# IO_board-ha-v1.net
KiCad netlist of a schematic drawn in EAGLE
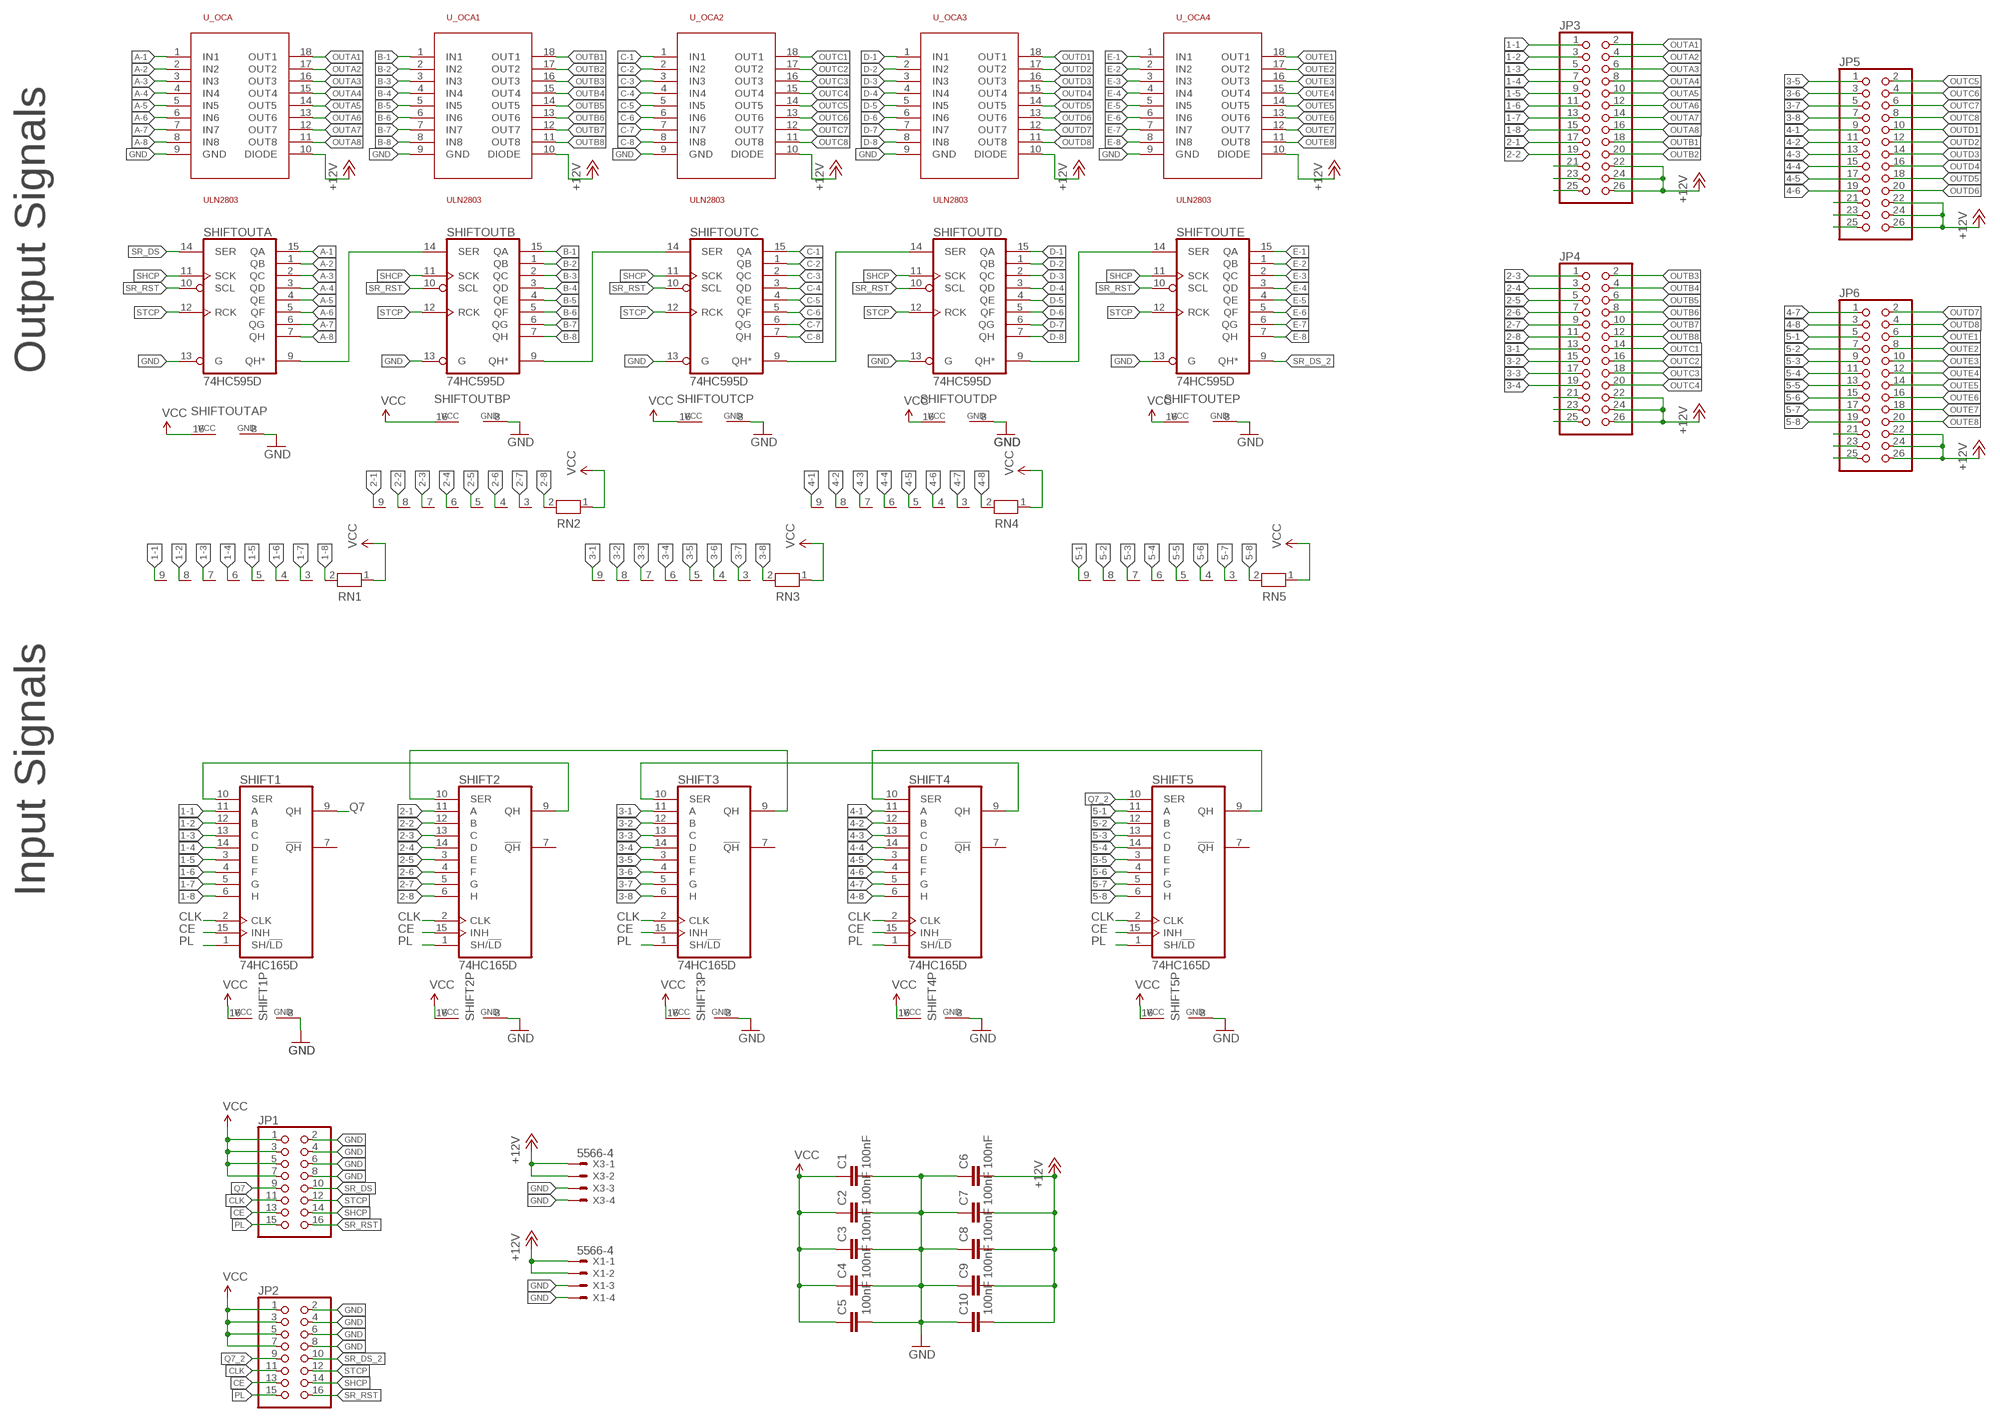
[diagram p0: schematic, sheet 1]

(export (version "E")
  (design (tool "Eeschema 10.0.6"))
  (components
    (comp (ref "C1")
      (value "100nF")
      (footprint "eagle-import:C0805")
      (libsource (lib "eagle-import") (part "C-EUC0805"))
    )
    (comp (ref "C2")
      (value "100nF")
      (footprint "eagle-import:C0805")
      (libsource (lib "eagle-import") (part "C-EUC0805"))
    )
    (comp (ref "C3")
      (value "100nF")
      (footprint "eagle-import:C0805")
      (libsource (lib "eagle-import") (part "C-EUC0805"))
    )
    (comp (ref "C4")
      (value "100nF")
      (footprint "eagle-import:C0805")
      (libsource (lib "eagle-import") (part "C-EUC0805"))
    )
    (comp (ref "C5")
      (value "100nF")
      (footprint "eagle-import:C0805")
      (libsource (lib "eagle-import") (part "C-EUC0805"))
    )
    (comp (ref "C6")
      (value "100nF")
      (footprint "eagle-import:C0805")
      (libsource (lib "eagle-import") (part "C-EUC0805"))
    )
    (comp (ref "C7")
      (value "100nF")
      (footprint "eagle-import:C0805")
      (libsource (lib "eagle-import") (part "C-EUC0805"))
    )
    (comp (ref "C8")
      (value "100nF")
      (footprint "eagle-import:C0805")
      (libsource (lib "eagle-import") (part "C-EUC0805"))
    )
    (comp (ref "C9")
      (value "100nF")
      (footprint "eagle-import:C0805")
      (libsource (lib "eagle-import") (part "C-EUC0805"))
    )
    (comp (ref "C10")
      (value "100nF")
      (footprint "eagle-import:C0805")
      (libsource (lib "eagle-import") (part "C-EUC0805"))
    )
    (comp (ref "JP1")
      (value "PINHD-2X8")
      (footprint "eagle-import:2X08")
      (libsource (lib "eagle-import") (part "PINHD-2X8"))
    )
    (comp (ref "JP2")
      (value "PINHD-2X8")
      (footprint "eagle-import:2X08")
      (libsource (lib "eagle-import") (part "PINHD-2X8"))
    )
    (comp (ref "JP3")
      (value "PINHD-2X13")
      (footprint "eagle-import:2X13")
      (libsource (lib "eagle-import") (part "PINHD-2X13"))
    )
    (comp (ref "JP4")
      (value "PINHD-2X13")
      (footprint "eagle-import:2X13")
      (libsource (lib "eagle-import") (part "PINHD-2X13"))
    )
    (comp (ref "JP5")
      (value "PINHD-2X13")
      (footprint "eagle-import:2X13")
      (libsource (lib "eagle-import") (part "PINHD-2X13"))
    )
    (comp (ref "JP6")
      (value "PINHD-2X13")
      (footprint "eagle-import:2X13")
      (libsource (lib "eagle-import") (part "PINHD-2X13"))
    )
    (comp (ref "RN1")
      (value "RN08")
      (footprint "eagle-import:RN-9")
      (libsource (lib "eagle-import") (part "RN08"))
    )
    (comp (ref "RN2")
      (value "RN08")
      (footprint "eagle-import:RN-9")
      (libsource (lib "eagle-import") (part "RN08"))
    )
    (comp (ref "RN3")
      (value "RN08")
      (footprint "eagle-import:RN-9")
      (libsource (lib "eagle-import") (part "RN08"))
    )
    (comp (ref "RN4")
      (value "RN08")
      (footprint "eagle-import:RN-9")
      (libsource (lib "eagle-import") (part "RN08"))
    )
    (comp (ref "RN5")
      (value "RN08")
      (footprint "eagle-import:RN-9")
      (libsource (lib "eagle-import") (part "RN08"))
    )
    (comp (ref "SHIFT1")
      (value "74HC165D")
      (footprint "eagle-import:SO16")
      (libsource (lib "eagle-import") (part "74165DHC"))
    )
    (comp (ref "SHIFT2")
      (value "74HC165D")
      (footprint "eagle-import:SO16")
      (libsource (lib "eagle-import") (part "74165DHC"))
    )
    (comp (ref "SHIFT3")
      (value "74HC165D")
      (footprint "eagle-import:SO16")
      (libsource (lib "eagle-import") (part "74165DHC"))
    )
    (comp (ref "SHIFT4")
      (value "74HC165D")
      (footprint "eagle-import:SO16")
      (libsource (lib "eagle-import") (part "74165DHC"))
    )
    (comp (ref "SHIFT5")
      (value "74HC165D")
      (footprint "eagle-import:SO16")
      (libsource (lib "eagle-import") (part "74165DHC"))
    )
    (comp (ref "SHIFTOUTA")
      (value "74HC595D")
      (footprint "eagle-import:SO16")
      (libsource (lib "eagle-import") (part "74595DHC"))
    )
    (comp (ref "SHIFTOUTB")
      (value "74HC595D")
      (footprint "eagle-import:SO16")
      (libsource (lib "eagle-import") (part "74595DHC"))
    )
    (comp (ref "SHIFTOUTC")
      (value "74HC595D")
      (footprint "eagle-import:SO16")
      (libsource (lib "eagle-import") (part "74595DHC"))
    )
    (comp (ref "SHIFTOUTD")
      (value "74HC595D")
      (footprint "eagle-import:SO16")
      (libsource (lib "eagle-import") (part "74595DHC"))
    )
    (comp (ref "SHIFTOUTE")
      (value "74HC595D")
      (footprint "eagle-import:SO16")
      (libsource (lib "eagle-import") (part "74595DHC"))
    )
    (comp (ref "U_OCA")
      (value "ULN2803")
      (footprint "eagle-import:SO18L")
      (libsource (lib "eagle-import") (part "ULN2803"))
    )
    (comp (ref "U_OCA1")
      (value "ULN2803")
      (footprint "eagle-import:SO18L")
      (libsource (lib "eagle-import") (part "ULN2803"))
    )
    (comp (ref "U_OCA2")
      (value "ULN2803")
      (footprint "eagle-import:SO18L")
      (libsource (lib "eagle-import") (part "ULN2803"))
    )
    (comp (ref "U_OCA3")
      (value "ULN2803")
      (footprint "eagle-import:SO18L")
      (libsource (lib "eagle-import") (part "ULN2803"))
    )
    (comp (ref "U_OCA4")
      (value "ULN2803")
      (footprint "eagle-import:SO18L")
      (libsource (lib "eagle-import") (part "ULN2803"))
    )
    (comp (ref "X1")
      (value "5566-4")
      (footprint "eagle-import:5566-4")
      (libsource (lib "eagle-import") (part "5566-4"))
    )
    (comp (ref "X3")
      (value "5566-4")
      (footprint "eagle-import:5566-4")
      (libsource (lib "eagle-import") (part "5566-4"))
    )
  )
  (nets
    (net (code "1") (name "+12V") (class "Default")
      (node (ref "C10") (pin "2") (pinfunction "2_2") (pintype "passive"))
      (node (ref "C6") (pin "2") (pinfunction "2_2") (pintype "passive"))
      (node (ref "C7") (pin "2") (pinfunction "2_2") (pintype "passive"))
      (node (ref "C8") (pin "2") (pinfunction "2_2") (pintype "passive"))
      (node (ref "C9") (pin "2") (pinfunction "2_2") (pintype "passive"))
      (node (ref "JP3") (pin "22") (pinfunction "22_22") (pintype "passive"))
      (node (ref "JP3") (pin "24") (pinfunction "24_24") (pintype "passive"))
      (node (ref "JP3") (pin "26") (pinfunction "26_26") (pintype "passive"))
      (node (ref "JP4") (pin "22") (pinfunction "22_22") (pintype "passive"))
      (node (ref "JP4") (pin "24") (pinfunction "24_24") (pintype "passive"))
      (node (ref "JP4") (pin "26") (pinfunction "26_26") (pintype "passive"))
      (node (ref "JP5") (pin "22") (pinfunction "22_22") (pintype "passive"))
      (node (ref "JP5") (pin "24") (pinfunction "24_24") (pintype "passive"))
      (node (ref "JP5") (pin "26") (pinfunction "26_26") (pintype "passive"))
      (node (ref "JP6") (pin "22") (pinfunction "22_22") (pintype "passive"))
      (node (ref "JP6") (pin "24") (pinfunction "24_24") (pintype "passive"))
      (node (ref "JP6") (pin "26") (pinfunction "26_26") (pintype "passive"))
      (node (ref "U_OCA") (pin "10") (pinfunction "DIODE_10") (pintype "power_in"))
      (node (ref "U_OCA1") (pin "10") (pinfunction "DIODE_10") (pintype "power_in"))
      (node (ref "U_OCA2") (pin "10") (pinfunction "DIODE_10") (pintype "power_in"))
      (node (ref "U_OCA3") (pin "10") (pinfunction "DIODE_10") (pintype "power_in"))
      (node (ref "U_OCA4") (pin "10") (pinfunction "DIODE_10") (pintype "power_in"))
      (node (ref "X1") (pin "1") (pinfunction "S_1") (pintype "passive"))
      (node (ref "X1") (pin "2") (pinfunction "S_2") (pintype "passive"))
      (node (ref "X3") (pin "1") (pinfunction "S_1") (pintype "passive"))
      (node (ref "X3") (pin "2") (pinfunction "S_2") (pintype "passive"))
    )
    (net (code "2") (name "1-1") (class "Default")
      (node (ref "JP3") (pin "1") (pinfunction "1_1") (pintype "passive"))
      (node (ref "RN1") (pin "9") (pinfunction "9_9") (pintype "passive"))
      (node (ref "SHIFT1") (pin "11") (pinfunction "A_11") (pintype "input"))
    )
    (net (code "3") (name "1-2") (class "Default")
      (node (ref "JP3") (pin "3") (pinfunction "3_3") (pintype "passive"))
      (node (ref "RN1") (pin "8") (pinfunction "8_8") (pintype "passive"))
      (node (ref "SHIFT1") (pin "12") (pinfunction "B_12") (pintype "input"))
    )
    (net (code "4") (name "1-3") (class "Default")
      (node (ref "JP3") (pin "5") (pinfunction "5_5") (pintype "passive"))
      (node (ref "RN1") (pin "7") (pinfunction "7_7") (pintype "passive"))
      (node (ref "SHIFT1") (pin "13") (pinfunction "C_13") (pintype "input"))
    )
    (net (code "5") (name "1-4") (class "Default")
      (node (ref "JP3") (pin "7") (pinfunction "7_7") (pintype "passive"))
      (node (ref "RN1") (pin "6") (pinfunction "6_6") (pintype "passive"))
      (node (ref "SHIFT1") (pin "14") (pinfunction "D_14") (pintype "input"))
    )
    (net (code "6") (name "1-5") (class "Default")
      (node (ref "JP3") (pin "9") (pinfunction "9_9") (pintype "passive"))
      (node (ref "RN1") (pin "5") (pinfunction "5_5") (pintype "passive"))
      (node (ref "SHIFT1") (pin "3") (pinfunction "E_3") (pintype "input"))
    )
    (net (code "7") (name "1-6") (class "Default")
      (node (ref "JP3") (pin "11") (pinfunction "11_11") (pintype "passive"))
      (node (ref "RN1") (pin "4") (pinfunction "4_4") (pintype "passive"))
      (node (ref "SHIFT1") (pin "4") (pinfunction "F_4") (pintype "input"))
    )
    (net (code "8") (name "1-7") (class "Default")
      (node (ref "JP3") (pin "13") (pinfunction "13_13") (pintype "passive"))
      (node (ref "RN1") (pin "3") (pinfunction "3_3") (pintype "passive"))
      (node (ref "SHIFT1") (pin "5") (pinfunction "G_5") (pintype "input"))
    )
    (net (code "9") (name "1-8") (class "Default")
      (node (ref "JP3") (pin "15") (pinfunction "15_15") (pintype "passive"))
      (node (ref "RN1") (pin "2") (pinfunction "2_2") (pintype "passive"))
      (node (ref "SHIFT1") (pin "6") (pinfunction "H_6") (pintype "input"))
    )
    (net (code "10") (name "2-1") (class "Default")
      (node (ref "JP3") (pin "17") (pinfunction "17_17") (pintype "passive"))
      (node (ref "RN2") (pin "9") (pinfunction "9_9") (pintype "passive"))
      (node (ref "SHIFT2") (pin "11") (pinfunction "A_11") (pintype "input"))
    )
    (net (code "11") (name "2-2") (class "Default")
      (node (ref "JP3") (pin "19") (pinfunction "19_19") (pintype "passive"))
      (node (ref "RN2") (pin "8") (pinfunction "8_8") (pintype "passive"))
      (node (ref "SHIFT2") (pin "12") (pinfunction "B_12") (pintype "input"))
    )
    (net (code "12") (name "2-3") (class "Default")
      (node (ref "JP4") (pin "1") (pinfunction "1_1") (pintype "passive"))
      (node (ref "RN2") (pin "7") (pinfunction "7_7") (pintype "passive"))
      (node (ref "SHIFT2") (pin "13") (pinfunction "C_13") (pintype "input"))
    )
    (net (code "13") (name "2-4") (class "Default")
      (node (ref "JP4") (pin "3") (pinfunction "3_3") (pintype "passive"))
      (node (ref "RN2") (pin "6") (pinfunction "6_6") (pintype "passive"))
      (node (ref "SHIFT2") (pin "14") (pinfunction "D_14") (pintype "input"))
    )
    (net (code "14") (name "2-5") (class "Default")
      (node (ref "JP4") (pin "5") (pinfunction "5_5") (pintype "passive"))
      (node (ref "RN2") (pin "5") (pinfunction "5_5") (pintype "passive"))
      (node (ref "SHIFT2") (pin "3") (pinfunction "E_3") (pintype "input"))
    )
    (net (code "15") (name "2-6") (class "Default")
      (node (ref "JP4") (pin "7") (pinfunction "7_7") (pintype "passive"))
      (node (ref "RN2") (pin "4") (pinfunction "4_4") (pintype "passive"))
      (node (ref "SHIFT2") (pin "4") (pinfunction "F_4") (pintype "input"))
    )
    (net (code "16") (name "2-7") (class "Default")
      (node (ref "JP4") (pin "9") (pinfunction "9_9") (pintype "passive"))
      (node (ref "RN2") (pin "3") (pinfunction "3_3") (pintype "passive"))
      (node (ref "SHIFT2") (pin "5") (pinfunction "G_5") (pintype "input"))
    )
    (net (code "17") (name "2-8") (class "Default")
      (node (ref "JP4") (pin "11") (pinfunction "11_11") (pintype "passive"))
      (node (ref "RN2") (pin "2") (pinfunction "2_2") (pintype "passive"))
      (node (ref "SHIFT2") (pin "6") (pinfunction "H_6") (pintype "input"))
    )
    (net (code "18") (name "3-1") (class "Default")
      (node (ref "JP4") (pin "13") (pinfunction "13_13") (pintype "passive"))
      (node (ref "RN3") (pin "9") (pinfunction "9_9") (pintype "passive"))
      (node (ref "SHIFT3") (pin "11") (pinfunction "A_11") (pintype "input"))
    )
    (net (code "19") (name "3-2") (class "Default")
      (node (ref "JP4") (pin "15") (pinfunction "15_15") (pintype "passive"))
      (node (ref "RN3") (pin "8") (pinfunction "8_8") (pintype "passive"))
      (node (ref "SHIFT3") (pin "12") (pinfunction "B_12") (pintype "input"))
    )
    (net (code "20") (name "3-3") (class "Default")
      (node (ref "JP4") (pin "17") (pinfunction "17_17") (pintype "passive"))
      (node (ref "RN3") (pin "7") (pinfunction "7_7") (pintype "passive"))
      (node (ref "SHIFT3") (pin "13") (pinfunction "C_13") (pintype "input"))
    )
    (net (code "21") (name "3-4") (class "Default")
      (node (ref "JP4") (pin "19") (pinfunction "19_19") (pintype "passive"))
      (node (ref "RN3") (pin "6") (pinfunction "6_6") (pintype "passive"))
      (node (ref "SHIFT3") (pin "14") (pinfunction "D_14") (pintype "input"))
    )
    (net (code "22") (name "3-5") (class "Default")
      (node (ref "JP5") (pin "1") (pinfunction "1_1") (pintype "passive"))
      (node (ref "RN3") (pin "5") (pinfunction "5_5") (pintype "passive"))
      (node (ref "SHIFT3") (pin "3") (pinfunction "E_3") (pintype "input"))
    )
    (net (code "23") (name "3-6") (class "Default")
      (node (ref "JP5") (pin "3") (pinfunction "3_3") (pintype "passive"))
      (node (ref "RN3") (pin "4") (pinfunction "4_4") (pintype "passive"))
      (node (ref "SHIFT3") (pin "4") (pinfunction "F_4") (pintype "input"))
    )
    (net (code "24") (name "3-7") (class "Default")
      (node (ref "JP5") (pin "5") (pinfunction "5_5") (pintype "passive"))
      (node (ref "RN3") (pin "3") (pinfunction "3_3") (pintype "passive"))
      (node (ref "SHIFT3") (pin "5") (pinfunction "G_5") (pintype "input"))
    )
    (net (code "25") (name "3-8") (class "Default")
      (node (ref "JP5") (pin "7") (pinfunction "7_7") (pintype "passive"))
      (node (ref "RN3") (pin "2") (pinfunction "2_2") (pintype "passive"))
      (node (ref "SHIFT3") (pin "6") (pinfunction "H_6") (pintype "input"))
    )
    (net (code "26") (name "4-1") (class "Default")
      (node (ref "JP5") (pin "9") (pinfunction "9_9") (pintype "passive"))
      (node (ref "RN4") (pin "9") (pinfunction "9_9") (pintype "passive"))
      (node (ref "SHIFT4") (pin "11") (pinfunction "A_11") (pintype "input"))
    )
    (net (code "27") (name "4-2") (class "Default")
      (node (ref "JP5") (pin "11") (pinfunction "11_11") (pintype "passive"))
      (node (ref "RN4") (pin "8") (pinfunction "8_8") (pintype "passive"))
      (node (ref "SHIFT4") (pin "12") (pinfunction "B_12") (pintype "input"))
    )
    (net (code "28") (name "4-3") (class "Default")
      (node (ref "JP5") (pin "13") (pinfunction "13_13") (pintype "passive"))
      (node (ref "RN4") (pin "7") (pinfunction "7_7") (pintype "passive"))
      (node (ref "SHIFT4") (pin "13") (pinfunction "C_13") (pintype "input"))
    )
    (net (code "29") (name "4-4") (class "Default")
      (node (ref "JP5") (pin "15") (pinfunction "15_15") (pintype "passive"))
      (node (ref "RN4") (pin "6") (pinfunction "6_6") (pintype "passive"))
      (node (ref "SHIFT4") (pin "14") (pinfunction "D_14") (pintype "input"))
    )
    (net (code "30") (name "4-5") (class "Default")
      (node (ref "JP5") (pin "17") (pinfunction "17_17") (pintype "passive"))
      (node (ref "RN4") (pin "5") (pinfunction "5_5") (pintype "passive"))
      (node (ref "SHIFT4") (pin "3") (pinfunction "E_3") (pintype "input"))
    )
    (net (code "31") (name "4-6") (class "Default")
      (node (ref "JP5") (pin "19") (pinfunction "19_19") (pintype "passive"))
      (node (ref "RN4") (pin "4") (pinfunction "4_4") (pintype "passive"))
      (node (ref "SHIFT4") (pin "4") (pinfunction "F_4") (pintype "input"))
    )
    (net (code "32") (name "4-7") (class "Default")
      (node (ref "JP6") (pin "1") (pinfunction "1_1") (pintype "passive"))
      (node (ref "RN4") (pin "3") (pinfunction "3_3") (pintype "passive"))
      (node (ref "SHIFT4") (pin "5") (pinfunction "G_5") (pintype "input"))
    )
    (net (code "33") (name "4-8") (class "Default")
      (node (ref "JP6") (pin "3") (pinfunction "3_3") (pintype "passive"))
      (node (ref "RN4") (pin "2") (pinfunction "2_2") (pintype "passive"))
      (node (ref "SHIFT4") (pin "6") (pinfunction "H_6") (pintype "input"))
    )
    (net (code "34") (name "5-1") (class "Default")
      (node (ref "JP6") (pin "5") (pinfunction "5_5") (pintype "passive"))
      (node (ref "RN5") (pin "9") (pinfunction "9_9") (pintype "passive"))
      (node (ref "SHIFT5") (pin "11") (pinfunction "A_11") (pintype "input"))
    )
    (net (code "35") (name "5-2") (class "Default")
      (node (ref "JP6") (pin "7") (pinfunction "7_7") (pintype "passive"))
      (node (ref "RN5") (pin "8") (pinfunction "8_8") (pintype "passive"))
      (node (ref "SHIFT5") (pin "12") (pinfunction "B_12") (pintype "input"))
    )
    (net (code "36") (name "5-3") (class "Default")
      (node (ref "JP6") (pin "9") (pinfunction "9_9") (pintype "passive"))
      (node (ref "RN5") (pin "7") (pinfunction "7_7") (pintype "passive"))
      (node (ref "SHIFT5") (pin "13") (pinfunction "C_13") (pintype "input"))
    )
    (net (code "37") (name "5-4") (class "Default")
      (node (ref "JP6") (pin "11") (pinfunction "11_11") (pintype "passive"))
      (node (ref "RN5") (pin "6") (pinfunction "6_6") (pintype "passive"))
      (node (ref "SHIFT5") (pin "14") (pinfunction "D_14") (pintype "input"))
    )
    (net (code "38") (name "5-5") (class "Default")
      (node (ref "JP6") (pin "13") (pinfunction "13_13") (pintype "passive"))
      (node (ref "RN5") (pin "5") (pinfunction "5_5") (pintype "passive"))
      (node (ref "SHIFT5") (pin "3") (pinfunction "E_3") (pintype "input"))
    )
    (net (code "39") (name "5-6") (class "Default")
      (node (ref "JP6") (pin "15") (pinfunction "15_15") (pintype "passive"))
      (node (ref "RN5") (pin "4") (pinfunction "4_4") (pintype "passive"))
      (node (ref "SHIFT5") (pin "4") (pinfunction "F_4") (pintype "input"))
    )
    (net (code "40") (name "5-7") (class "Default")
      (node (ref "JP6") (pin "17") (pinfunction "17_17") (pintype "passive"))
      (node (ref "RN5") (pin "3") (pinfunction "3_3") (pintype "passive"))
      (node (ref "SHIFT5") (pin "5") (pinfunction "G_5") (pintype "input"))
    )
    (net (code "41") (name "5-8") (class "Default")
      (node (ref "JP6") (pin "19") (pinfunction "19_19") (pintype "passive"))
      (node (ref "RN5") (pin "2") (pinfunction "2_2") (pintype "passive"))
      (node (ref "SHIFT5") (pin "6") (pinfunction "H_6") (pintype "input"))
    )
    (net (code "42") (name "A-1") (class "Default")
      (node (ref "SHIFTOUTA") (pin "15") (pinfunction "QA_15") (pintype "tri_state"))
      (node (ref "U_OCA") (pin "1") (pinfunction "IN1_1") (pintype "input"))
    )
    (net (code "43") (name "A-2") (class "Default")
      (node (ref "SHIFTOUTA") (pin "1") (pinfunction "QB_1") (pintype "tri_state"))
      (node (ref "U_OCA") (pin "2") (pinfunction "IN2_2") (pintype "input"))
    )
    (net (code "44") (name "A-3") (class "Default")
      (node (ref "SHIFTOUTA") (pin "2") (pinfunction "QC_2") (pintype "tri_state"))
      (node (ref "U_OCA") (pin "3") (pinfunction "IN3_3") (pintype "input"))
    )
    (net (code "45") (name "A-4") (class "Default")
      (node (ref "SHIFTOUTA") (pin "3") (pinfunction "QD_3") (pintype "tri_state"))
      (node (ref "U_OCA") (pin "4") (pinfunction "IN4_4") (pintype "input"))
    )
    (net (code "46") (name "A-5") (class "Default")
      (node (ref "SHIFTOUTA") (pin "4") (pinfunction "QE_4") (pintype "tri_state"))
      (node (ref "U_OCA") (pin "5") (pinfunction "IN5_5") (pintype "input"))
    )
    (net (code "47") (name "A-6") (class "Default")
      (node (ref "SHIFTOUTA") (pin "5") (pinfunction "QF_5") (pintype "tri_state"))
      (node (ref "U_OCA") (pin "6") (pinfunction "IN6_6") (pintype "input"))
    )
    (net (code "48") (name "A-7") (class "Default")
      (node (ref "SHIFTOUTA") (pin "6") (pinfunction "QG_6") (pintype "tri_state"))
      (node (ref "U_OCA") (pin "7") (pinfunction "IN7_7") (pintype "input"))
    )
    (net (code "49") (name "A-8") (class "Default")
      (node (ref "SHIFTOUTA") (pin "7") (pinfunction "QH_7") (pintype "tri_state"))
      (node (ref "U_OCA") (pin "8") (pinfunction "IN8_8") (pintype "input"))
    )
    (net (code "50") (name "B-1") (class "Default")
      (node (ref "SHIFTOUTB") (pin "15") (pinfunction "QA_15") (pintype "tri_state"))
      (node (ref "U_OCA1") (pin "1") (pinfunction "IN1_1") (pintype "input"))
    )
    (net (code "51") (name "B-2") (class "Default")
      (node (ref "SHIFTOUTB") (pin "1") (pinfunction "QB_1") (pintype "tri_state"))
      (node (ref "U_OCA1") (pin "2") (pinfunction "IN2_2") (pintype "input"))
    )
    (net (code "52") (name "B-3") (class "Default")
      (node (ref "SHIFTOUTB") (pin "2") (pinfunction "QC_2") (pintype "tri_state"))
      (node (ref "U_OCA1") (pin "3") (pinfunction "IN3_3") (pintype "input"))
    )
    (net (code "53") (name "B-4") (class "Default")
      (node (ref "SHIFTOUTB") (pin "3") (pinfunction "QD_3") (pintype "tri_state"))
      (node (ref "U_OCA1") (pin "4") (pinfunction "IN4_4") (pintype "input"))
    )
    (net (code "54") (name "B-5") (class "Default")
      (node (ref "SHIFTOUTB") (pin "4") (pinfunction "QE_4") (pintype "tri_state"))
      (node (ref "U_OCA1") (pin "5") (pinfunction "IN5_5") (pintype "input"))
    )
    (net (code "55") (name "B-6") (class "Default")
      (node (ref "SHIFTOUTB") (pin "5") (pinfunction "QF_5") (pintype "tri_state"))
      (node (ref "U_OCA1") (pin "6") (pinfunction "IN6_6") (pintype "input"))
    )
    (net (code "56") (name "B-7") (class "Default")
      (node (ref "SHIFTOUTB") (pin "6") (pinfunction "QG_6") (pintype "tri_state"))
      (node (ref "U_OCA1") (pin "7") (pinfunction "IN7_7") (pintype "input"))
    )
    (net (code "57") (name "B-8") (class "Default")
      (node (ref "SHIFTOUTB") (pin "7") (pinfunction "QH_7") (pintype "tri_state"))
      (node (ref "U_OCA1") (pin "8") (pinfunction "IN8_8") (pintype "input"))
    )
    (net (code "58") (name "C-1") (class "Default")
      (node (ref "SHIFTOUTC") (pin "15") (pinfunction "QA_15") (pintype "tri_state"))
      (node (ref "U_OCA2") (pin "1") (pinfunction "IN1_1") (pintype "input"))
    )
    (net (code "59") (name "C-2") (class "Default")
      (node (ref "SHIFTOUTC") (pin "1") (pinfunction "QB_1") (pintype "tri_state"))
      (node (ref "U_OCA2") (pin "2") (pinfunction "IN2_2") (pintype "input"))
    )
    (net (code "60") (name "C-3") (class "Default")
      (node (ref "SHIFTOUTC") (pin "2") (pinfunction "QC_2") (pintype "tri_state"))
      (node (ref "U_OCA2") (pin "3") (pinfunction "IN3_3") (pintype "input"))
    )
    (net (code "61") (name "C-4") (class "Default")
      (node (ref "SHIFTOUTC") (pin "3") (pinfunction "QD_3") (pintype "tri_state"))
      (node (ref "U_OCA2") (pin "4") (pinfunction "IN4_4") (pintype "input"))
    )
    (net (code "62") (name "C-5") (class "Default")
      (node (ref "SHIFTOUTC") (pin "4") (pinfunction "QE_4") (pintype "tri_state"))
      (node (ref "U_OCA2") (pin "5") (pinfunction "IN5_5") (pintype "input"))
    )
    (net (code "63") (name "C-6") (class "Default")
      (node (ref "SHIFTOUTC") (pin "5") (pinfunction "QF_5") (pintype "tri_state"))
      (node (ref "U_OCA2") (pin "6") (pinfunction "IN6_6") (pintype "input"))
    )
    (net (code "64") (name "C-7") (class "Default")
      (node (ref "SHIFTOUTC") (pin "6") (pinfunction "QG_6") (pintype "tri_state"))
      (node (ref "U_OCA2") (pin "7") (pinfunction "IN7_7") (pintype "input"))
    )
    (net (code "65") (name "C-8") (class "Default")
      (node (ref "SHIFTOUTC") (pin "7") (pinfunction "QH_7") (pintype "tri_state"))
      (node (ref "U_OCA2") (pin "8") (pinfunction "IN8_8") (pintype "input"))
    )
    (net (code "66") (name "CE") (class "Default")
      (node (ref "JP1") (pin "13") (pinfunction "13_13") (pintype "passive"))
      (node (ref "JP2") (pin "13") (pinfunction "13_13") (pintype "passive"))
      (node (ref "SHIFT1") (pin "15") (pinfunction "INH_15") (pintype "input"))
      (node (ref "SHIFT2") (pin "15") (pinfunction "INH_15") (pintype "input"))
      (node (ref "SHIFT3") (pin "15") (pinfunction "INH_15") (pintype "input"))
      (node (ref "SHIFT4") (pin "15") (pinfunction "INH_15") (pintype "input"))
      (node (ref "SHIFT5") (pin "15") (pinfunction "INH_15") (pintype "input"))
    )
    (net (code "67") (name "CLK") (class "Default")
      (node (ref "JP1") (pin "11") (pinfunction "11_11") (pintype "passive"))
      (node (ref "JP2") (pin "11") (pinfunction "11_11") (pintype "passive"))
      (node (ref "SHIFT1") (pin "2") (pinfunction "CLK_2") (pintype "input"))
      (node (ref "SHIFT2") (pin "2") (pinfunction "CLK_2") (pintype "input"))
      (node (ref "SHIFT3") (pin "2") (pinfunction "CLK_2") (pintype "input"))
      (node (ref "SHIFT4") (pin "2") (pinfunction "CLK_2") (pintype "input"))
      (node (ref "SHIFT5") (pin "2") (pinfunction "CLK_2") (pintype "input"))
    )
    (net (code "68") (name "D-1") (class "Default")
      (node (ref "SHIFTOUTD") (pin "15") (pinfunction "QA_15") (pintype "tri_state"))
      (node (ref "U_OCA3") (pin "1") (pinfunction "IN1_1") (pintype "input"))
    )
    (net (code "69") (name "D-2") (class "Default")
      (node (ref "SHIFTOUTD") (pin "1") (pinfunction "QB_1") (pintype "tri_state"))
      (node (ref "U_OCA3") (pin "2") (pinfunction "IN2_2") (pintype "input"))
    )
    (net (code "70") (name "D-3") (class "Default")
      (node (ref "SHIFTOUTD") (pin "2") (pinfunction "QC_2") (pintype "tri_state"))
      (node (ref "U_OCA3") (pin "3") (pinfunction "IN3_3") (pintype "input"))
    )
    (net (code "71") (name "D-4") (class "Default")
      (node (ref "SHIFTOUTD") (pin "3") (pinfunction "QD_3") (pintype "tri_state"))
      (node (ref "U_OCA3") (pin "4") (pinfunction "IN4_4") (pintype "input"))
    )
    (net (code "72") (name "D-5") (class "Default")
      (node (ref "SHIFTOUTD") (pin "4") (pinfunction "QE_4") (pintype "tri_state"))
      (node (ref "U_OCA3") (pin "5") (pinfunction "IN5_5") (pintype "input"))
    )
    (net (code "73") (name "D-6") (class "Default")
      (node (ref "SHIFTOUTD") (pin "5") (pinfunction "QF_5") (pintype "tri_state"))
      (node (ref "U_OCA3") (pin "6") (pinfunction "IN6_6") (pintype "input"))
    )
    (net (code "74") (name "D-7") (class "Default")
      (node (ref "SHIFTOUTD") (pin "6") (pinfunction "QG_6") (pintype "tri_state"))
      (node (ref "U_OCA3") (pin "7") (pinfunction "IN7_7") (pintype "input"))
    )
    (net (code "75") (name "D-8") (class "Default")
      (node (ref "SHIFTOUTD") (pin "7") (pinfunction "QH_7") (pintype "tri_state"))
      (node (ref "U_OCA3") (pin "8") (pinfunction "IN8_8") (pintype "input"))
    )
    (net (code "76") (name "E-1") (class "Default")
      (node (ref "SHIFTOUTE") (pin "15") (pinfunction "QA_15") (pintype "tri_state"))
      (node (ref "U_OCA4") (pin "1") (pinfunction "IN1_1") (pintype "input"))
    )
    (net (code "77") (name "E-2") (class "Default")
      (node (ref "SHIFTOUTE") (pin "1") (pinfunction "QB_1") (pintype "tri_state"))
      (node (ref "U_OCA4") (pin "2") (pinfunction "IN2_2") (pintype "input"))
    )
    (net (code "78") (name "E-3") (class "Default")
      (node (ref "SHIFTOUTE") (pin "2") (pinfunction "QC_2") (pintype "tri_state"))
      (node (ref "U_OCA4") (pin "3") (pinfunction "IN3_3") (pintype "input"))
    )
    (net (code "79") (name "E-4") (class "Default")
      (node (ref "SHIFTOUTE") (pin "3") (pinfunction "QD_3") (pintype "tri_state"))
      (node (ref "U_OCA4") (pin "4") (pinfunction "IN4_4") (pintype "input"))
    )
    (net (code "80") (name "E-5") (class "Default")
      (node (ref "SHIFTOUTE") (pin "4") (pinfunction "QE_4") (pintype "tri_state"))
      (node (ref "U_OCA4") (pin "5") (pinfunction "IN5_5") (pintype "input"))
    )
    (net (code "81") (name "E-6") (class "Default")
      (node (ref "SHIFTOUTE") (pin "5") (pinfunction "QF_5") (pintype "tri_state"))
      (node (ref "U_OCA4") (pin "6") (pinfunction "IN6_6") (pintype "input"))
    )
    (net (code "82") (name "E-7") (class "Default")
      (node (ref "SHIFTOUTE") (pin "6") (pinfunction "QG_6") (pintype "tri_state"))
      (node (ref "U_OCA4") (pin "7") (pinfunction "IN7_7") (pintype "input"))
    )
    (net (code "83") (name "E-8") (class "Default")
      (node (ref "SHIFTOUTE") (pin "7") (pinfunction "QH_7") (pintype "tri_state"))
      (node (ref "U_OCA4") (pin "8") (pinfunction "IN8_8") (pintype "input"))
    )
    (net (code "84") (name "GND") (class "Default")
      (node (ref "C1") (pin "2") (pinfunction "2_2") (pintype "passive"))
      (node (ref "C10") (pin "1") (pinfunction "1_1") (pintype "passive"))
      (node (ref "C2") (pin "2") (pinfunction "2_2") (pintype "passive"))
      (node (ref "C3") (pin "2") (pinfunction "2_2") (pintype "passive"))
      (node (ref "C4") (pin "2") (pinfunction "2_2") (pintype "passive"))
      (node (ref "C5") (pin "2") (pinfunction "2_2") (pintype "passive"))
      (node (ref "C6") (pin "1") (pinfunction "1_1") (pintype "passive"))
      (node (ref "C7") (pin "1") (pinfunction "1_1") (pintype "passive"))
      (node (ref "C8") (pin "1") (pinfunction "1_1") (pintype "passive"))
      (node (ref "C9") (pin "1") (pinfunction "1_1") (pintype "passive"))
      (node (ref "JP1") (pin "2") (pinfunction "2_2") (pintype "passive"))
      (node (ref "JP1") (pin "4") (pinfunction "4_4") (pintype "passive"))
      (node (ref "JP1") (pin "6") (pinfunction "6_6") (pintype "passive"))
      (node (ref "JP1") (pin "8") (pinfunction "8_8") (pintype "passive"))
      (node (ref "JP2") (pin "2") (pinfunction "2_2") (pintype "passive"))
      (node (ref "JP2") (pin "4") (pinfunction "4_4") (pintype "passive"))
      (node (ref "JP2") (pin "6") (pinfunction "6_6") (pintype "passive"))
      (node (ref "JP2") (pin "8") (pinfunction "8_8") (pintype "passive"))
      (node (ref "JP3") (pin "21") (pinfunction "21_21") (pintype "passive"))
      (node (ref "JP3") (pin "23") (pinfunction "23_23") (pintype "passive"))
      (node (ref "JP3") (pin "25") (pinfunction "25_25") (pintype "passive"))
      (node (ref "JP4") (pin "21") (pinfunction "21_21") (pintype "passive"))
      (node (ref "JP4") (pin "23") (pinfunction "23_23") (pintype "passive"))
      (node (ref "JP4") (pin "25") (pinfunction "25_25") (pintype "passive"))
      (node (ref "JP5") (pin "21") (pinfunction "21_21") (pintype "passive"))
      (node (ref "JP5") (pin "23") (pinfunction "23_23") (pintype "passive"))
      (node (ref "JP5") (pin "25") (pinfunction "25_25") (pintype "passive"))
      (node (ref "JP6") (pin "21") (pinfunction "21_21") (pintype "passive"))
      (node (ref "JP6") (pin "23") (pinfunction "23_23") (pintype "passive"))
      (node (ref "JP6") (pin "25") (pinfunction "25_25") (pintype "passive"))
      (node (ref "SHIFT1") (pin "8") (pinfunction "GND_8") (pintype "power_in"))
      (node (ref "SHIFT2") (pin "8") (pinfunction "GND_8") (pintype "power_in"))
      (node (ref "SHIFT3") (pin "8") (pinfunction "GND_8") (pintype "power_in"))
      (node (ref "SHIFT4") (pin "8") (pinfunction "GND_8") (pintype "power_in"))
      (node (ref "SHIFT5") (pin "8") (pinfunction "GND_8") (pintype "power_in"))
      (node (ref "SHIFTOUTA") (pin "13") (pinfunction "G_13") (pintype "input"))
      (node (ref "SHIFTOUTA") (pin "8") (pinfunction "GND_8") (pintype "power_in"))
      (node (ref "SHIFTOUTB") (pin "13") (pinfunction "G_13") (pintype "input"))
      (node (ref "SHIFTOUTB") (pin "8") (pinfunction "GND_8") (pintype "power_in"))
      (node (ref "SHIFTOUTC") (pin "13") (pinfunction "G_13") (pintype "input"))
      (node (ref "SHIFTOUTC") (pin "8") (pinfunction "GND_8") (pintype "power_in"))
      (node (ref "SHIFTOUTD") (pin "13") (pinfunction "G_13") (pintype "input"))
      (node (ref "SHIFTOUTD") (pin "8") (pinfunction "GND_8") (pintype "power_in"))
      (node (ref "SHIFTOUTE") (pin "13") (pinfunction "G_13") (pintype "input"))
      (node (ref "SHIFTOUTE") (pin "8") (pinfunction "GND_8") (pintype "power_in"))
      (node (ref "U_OCA") (pin "9") (pinfunction "GND_9") (pintype "power_in"))
      (node (ref "U_OCA1") (pin "9") (pinfunction "GND_9") (pintype "power_in"))
      (node (ref "U_OCA2") (pin "9") (pinfunction "GND_9") (pintype "power_in"))
      (node (ref "U_OCA3") (pin "9") (pinfunction "GND_9") (pintype "power_in"))
      (node (ref "U_OCA4") (pin "9") (pinfunction "GND_9") (pintype "power_in"))
      (node (ref "X1") (pin "3") (pinfunction "S_3") (pintype "passive"))
      (node (ref "X1") (pin "4") (pinfunction "S_4") (pintype "passive"))
      (node (ref "X3") (pin "3") (pinfunction "S_3") (pintype "passive"))
      (node (ref "X3") (pin "4") (pinfunction "S_4") (pintype "passive"))
    )
    (net (code "85") (name "Net-(SHIFT1A-SER)") (class "Default")
      (node (ref "SHIFT1") (pin "10") (pinfunction "SER_10") (pintype "input"))
      (node (ref "SHIFT2") (pin "9") (pinfunction "QH_9") (pintype "output"))
    )
    (net (code "86") (name "Net-(SHIFT2A-SER)") (class "Default")
      (node (ref "SHIFT2") (pin "10") (pinfunction "SER_10") (pintype "input"))
      (node (ref "SHIFT3") (pin "9") (pinfunction "QH_9") (pintype "output"))
    )
    (net (code "87") (name "Net-(SHIFT3A-SER)") (class "Default")
      (node (ref "SHIFT3") (pin "10") (pinfunction "SER_10") (pintype "input"))
      (node (ref "SHIFT4") (pin "9") (pinfunction "QH_9") (pintype "output"))
    )
    (net (code "88") (name "Net-(SHIFT4A-SER)") (class "Default")
      (node (ref "SHIFT4") (pin "10") (pinfunction "SER_10") (pintype "input"))
      (node (ref "SHIFT5") (pin "9") (pinfunction "QH_9") (pintype "output"))
    )
    (net (code "89") (name "Net-(SHIFTOUTAA-QH*)") (class "Default")
      (node (ref "SHIFTOUTA") (pin "9") (pinfunction "QH*_9") (pintype "tri_state"))
      (node (ref "SHIFTOUTB") (pin "14") (pinfunction "SER_14") (pintype "input"))
    )
    (net (code "90") (name "Net-(SHIFTOUTBA-QH*)") (class "Default")
      (node (ref "SHIFTOUTB") (pin "9") (pinfunction "QH*_9") (pintype "tri_state"))
      (node (ref "SHIFTOUTC") (pin "14") (pinfunction "SER_14") (pintype "input"))
    )
    (net (code "91") (name "Net-(SHIFTOUTCA-QH*)") (class "Default")
      (node (ref "SHIFTOUTC") (pin "9") (pinfunction "QH*_9") (pintype "tri_state"))
      (node (ref "SHIFTOUTD") (pin "14") (pinfunction "SER_14") (pintype "input"))
    )
    (net (code "92") (name "Net-(SHIFTOUTDA-QH*)") (class "Default")
      (node (ref "SHIFTOUTD") (pin "9") (pinfunction "QH*_9") (pintype "tri_state"))
      (node (ref "SHIFTOUTE") (pin "14") (pinfunction "SER_14") (pintype "input"))
    )
    (net (code "93") (name "OUTA1") (class "Default")
      (node (ref "JP3") (pin "2") (pinfunction "2_2") (pintype "passive"))
      (node (ref "U_OCA") (pin "18") (pinfunction "OUT1_18") (pintype "open_collector"))
    )
    (net (code "94") (name "OUTA2") (class "Default")
      (node (ref "JP3") (pin "4") (pinfunction "4_4") (pintype "passive"))
      (node (ref "U_OCA") (pin "17") (pinfunction "OUT2_17") (pintype "open_collector"))
    )
    (net (code "95") (name "OUTA3") (class "Default")
      (node (ref "JP3") (pin "6") (pinfunction "6_6") (pintype "passive"))
      (node (ref "U_OCA") (pin "16") (pinfunction "OUT3_16") (pintype "open_collector"))
    )
    (net (code "96") (name "OUTA4") (class "Default")
      (node (ref "JP3") (pin "8") (pinfunction "8_8") (pintype "passive"))
      (node (ref "U_OCA") (pin "15") (pinfunction "OUT4_15") (pintype "open_collector"))
    )
    (net (code "97") (name "OUTA5") (class "Default")
      (node (ref "JP3") (pin "10") (pinfunction "10_10") (pintype "passive"))
      (node (ref "U_OCA") (pin "14") (pinfunction "OUT5_14") (pintype "open_collector"))
    )
    (net (code "98") (name "OUTA6") (class "Default")
      (node (ref "JP3") (pin "12") (pinfunction "12_12") (pintype "passive"))
      (node (ref "U_OCA") (pin "13") (pinfunction "OUT6_13") (pintype "open_collector"))
    )
    (net (code "99") (name "OUTA7") (class "Default")
      (node (ref "JP3") (pin "14") (pinfunction "14_14") (pintype "passive"))
      (node (ref "U_OCA") (pin "12") (pinfunction "OUT7_12") (pintype "open_collector"))
    )
    (net (code "100") (name "OUTA8") (class "Default")
      (node (ref "JP3") (pin "16") (pinfunction "16_16") (pintype "passive"))
      (node (ref "U_OCA") (pin "11") (pinfunction "OUT8_11") (pintype "open_collector"))
    )
    (net (code "101") (name "OUTB1") (class "Default")
      (node (ref "JP3") (pin "18") (pinfunction "18_18") (pintype "passive"))
      (node (ref "U_OCA1") (pin "18") (pinfunction "OUT1_18") (pintype "open_collector"))
    )
    (net (code "102") (name "OUTB2") (class "Default")
      (node (ref "JP3") (pin "20") (pinfunction "20_20") (pintype "passive"))
      (node (ref "U_OCA1") (pin "17") (pinfunction "OUT2_17") (pintype "open_collector"))
    )
    (net (code "103") (name "OUTB3") (class "Default")
      (node (ref "JP4") (pin "2") (pinfunction "2_2") (pintype "passive"))
      (node (ref "U_OCA1") (pin "16") (pinfunction "OUT3_16") (pintype "open_collector"))
    )
    (net (code "104") (name "OUTB4") (class "Default")
      (node (ref "JP4") (pin "4") (pinfunction "4_4") (pintype "passive"))
      (node (ref "U_OCA1") (pin "15") (pinfunction "OUT4_15") (pintype "open_collector"))
    )
    (net (code "105") (name "OUTB5") (class "Default")
      (node (ref "JP4") (pin "6") (pinfunction "6_6") (pintype "passive"))
      (node (ref "U_OCA1") (pin "14") (pinfunction "OUT5_14") (pintype "open_collector"))
    )
    (net (code "106") (name "OUTB6") (class "Default")
      (node (ref "JP4") (pin "8") (pinfunction "8_8") (pintype "passive"))
      (node (ref "U_OCA1") (pin "13") (pinfunction "OUT6_13") (pintype "open_collector"))
    )
    (net (code "107") (name "OUTB7") (class "Default")
      (node (ref "JP4") (pin "10") (pinfunction "10_10") (pintype "passive"))
      (node (ref "U_OCA1") (pin "12") (pinfunction "OUT7_12") (pintype "open_collector"))
    )
    (net (code "108") (name "OUTB8") (class "Default")
      (node (ref "JP4") (pin "12") (pinfunction "12_12") (pintype "passive"))
      (node (ref "U_OCA1") (pin "11") (pinfunction "OUT8_11") (pintype "open_collector"))
    )
    (net (code "109") (name "OUTC1") (class "Default")
      (node (ref "JP4") (pin "14") (pinfunction "14_14") (pintype "passive"))
      (node (ref "U_OCA2") (pin "18") (pinfunction "OUT1_18") (pintype "open_collector"))
    )
    (net (code "110") (name "OUTC2") (class "Default")
      (node (ref "JP4") (pin "16") (pinfunction "16_16") (pintype "passive"))
      (node (ref "U_OCA2") (pin "17") (pinfunction "OUT2_17") (pintype "open_collector"))
    )
    (net (code "111") (name "OUTC3") (class "Default")
      (node (ref "JP4") (pin "18") (pinfunction "18_18") (pintype "passive"))
      (node (ref "U_OCA2") (pin "16") (pinfunction "OUT3_16") (pintype "open_collector"))
    )
    (net (code "112") (name "OUTC4") (class "Default")
      (node (ref "JP4") (pin "20") (pinfunction "20_20") (pintype "passive"))
      (node (ref "U_OCA2") (pin "15") (pinfunction "OUT4_15") (pintype "open_collector"))
    )
    (net (code "113") (name "OUTC5") (class "Default")
      (node (ref "JP5") (pin "2") (pinfunction "2_2") (pintype "passive"))
      (node (ref "U_OCA2") (pin "14") (pinfunction "OUT5_14") (pintype "open_collector"))
    )
    (net (code "114") (name "OUTC6") (class "Default")
      (node (ref "JP5") (pin "4") (pinfunction "4_4") (pintype "passive"))
      (node (ref "U_OCA2") (pin "13") (pinfunction "OUT6_13") (pintype "open_collector"))
    )
    (net (code "115") (name "OUTC7") (class "Default")
      (node (ref "JP5") (pin "6") (pinfunction "6_6") (pintype "passive"))
      (node (ref "U_OCA2") (pin "12") (pinfunction "OUT7_12") (pintype "open_collector"))
    )
    (net (code "116") (name "OUTC8") (class "Default")
      (node (ref "JP5") (pin "8") (pinfunction "8_8") (pintype "passive"))
      (node (ref "U_OCA2") (pin "11") (pinfunction "OUT8_11") (pintype "open_collector"))
    )
    (net (code "117") (name "OUTD1") (class "Default")
      (node (ref "JP5") (pin "10") (pinfunction "10_10") (pintype "passive"))
      (node (ref "U_OCA3") (pin "18") (pinfunction "OUT1_18") (pintype "open_collector"))
    )
    (net (code "118") (name "OUTD2") (class "Default")
      (node (ref "JP5") (pin "12") (pinfunction "12_12") (pintype "passive"))
      (node (ref "U_OCA3") (pin "17") (pinfunction "OUT2_17") (pintype "open_collector"))
    )
    (net (code "119") (name "OUTD3") (class "Default")
      (node (ref "JP5") (pin "14") (pinfunction "14_14") (pintype "passive"))
      (node (ref "U_OCA3") (pin "16") (pinfunction "OUT3_16") (pintype "open_collector"))
    )
    (net (code "120") (name "OUTD4") (class "Default")
      (node (ref "JP5") (pin "16") (pinfunction "16_16") (pintype "passive"))
      (node (ref "U_OCA3") (pin "15") (pinfunction "OUT4_15") (pintype "open_collector"))
    )
    (net (code "121") (name "OUTD5") (class "Default")
      (node (ref "JP5") (pin "18") (pinfunction "18_18") (pintype "passive"))
      (node (ref "U_OCA3") (pin "14") (pinfunction "OUT5_14") (pintype "open_collector"))
    )
    (net (code "122") (name "OUTD6") (class "Default")
      (node (ref "JP5") (pin "20") (pinfunction "20_20") (pintype "passive"))
      (node (ref "U_OCA3") (pin "13") (pinfunction "OUT6_13") (pintype "open_collector"))
    )
    (net (code "123") (name "OUTD7") (class "Default")
      (node (ref "JP6") (pin "2") (pinfunction "2_2") (pintype "passive"))
      (node (ref "U_OCA3") (pin "12") (pinfunction "OUT7_12") (pintype "open_collector"))
    )
    (net (code "124") (name "OUTD8") (class "Default")
      (node (ref "JP6") (pin "4") (pinfunction "4_4") (pintype "passive"))
      (node (ref "U_OCA3") (pin "11") (pinfunction "OUT8_11") (pintype "open_collector"))
    )
    (net (code "125") (name "OUTE1") (class "Default")
      (node (ref "JP6") (pin "6") (pinfunction "6_6") (pintype "passive"))
      (node (ref "U_OCA4") (pin "18") (pinfunction "OUT1_18") (pintype "open_collector"))
    )
    (net (code "126") (name "OUTE2") (class "Default")
      (node (ref "JP6") (pin "8") (pinfunction "8_8") (pintype "passive"))
      (node (ref "U_OCA4") (pin "17") (pinfunction "OUT2_17") (pintype "open_collector"))
    )
    (net (code "127") (name "OUTE3") (class "Default")
      (node (ref "JP6") (pin "10") (pinfunction "10_10") (pintype "passive"))
      (node (ref "U_OCA4") (pin "16") (pinfunction "OUT3_16") (pintype "open_collector"))
    )
    (net (code "128") (name "OUTE4") (class "Default")
      (node (ref "JP6") (pin "12") (pinfunction "12_12") (pintype "passive"))
      (node (ref "U_OCA4") (pin "15") (pinfunction "OUT4_15") (pintype "open_collector"))
    )
    (net (code "129") (name "OUTE5") (class "Default")
      (node (ref "JP6") (pin "14") (pinfunction "14_14") (pintype "passive"))
      (node (ref "U_OCA4") (pin "14") (pinfunction "OUT5_14") (pintype "open_collector"))
    )
    (net (code "130") (name "OUTE6") (class "Default")
      (node (ref "JP6") (pin "16") (pinfunction "16_16") (pintype "passive"))
      (node (ref "U_OCA4") (pin "13") (pinfunction "OUT6_13") (pintype "open_collector"))
    )
    (net (code "131") (name "OUTE7") (class "Default")
      (node (ref "JP6") (pin "18") (pinfunction "18_18") (pintype "passive"))
      (node (ref "U_OCA4") (pin "12") (pinfunction "OUT7_12") (pintype "open_collector"))
    )
    (net (code "132") (name "OUTE8") (class "Default")
      (node (ref "JP6") (pin "20") (pinfunction "20_20") (pintype "passive"))
      (node (ref "U_OCA4") (pin "11") (pinfunction "OUT8_11") (pintype "open_collector"))
    )
    (net (code "133") (name "PL") (class "Default")
      (node (ref "JP1") (pin "15") (pinfunction "15_15") (pintype "passive"))
      (node (ref "JP2") (pin "15") (pinfunction "15_15") (pintype "passive"))
      (node (ref "SHIFT1") (pin "1") (pinfunction "SH/~{LD}_1") (pintype "input"))
      (node (ref "SHIFT2") (pin "1") (pinfunction "SH/~{LD}_1") (pintype "input"))
      (node (ref "SHIFT3") (pin "1") (pinfunction "SH/~{LD}_1") (pintype "input"))
      (node (ref "SHIFT4") (pin "1") (pinfunction "SH/~{LD}_1") (pintype "input"))
      (node (ref "SHIFT5") (pin "1") (pinfunction "SH/~{LD}_1") (pintype "input"))
    )
    (net (code "134") (name "Q7") (class "Default")
      (node (ref "JP1") (pin "9") (pinfunction "9_9") (pintype "passive"))
      (node (ref "SHIFT1") (pin "9") (pinfunction "QH_9") (pintype "output"))
    )
    (net (code "135") (name "Q7_2") (class "Default")
      (node (ref "JP2") (pin "9") (pinfunction "9_9") (pintype "passive"))
      (node (ref "SHIFT5") (pin "10") (pinfunction "SER_10") (pintype "input"))
    )
    (net (code "136") (name "SHCP") (class "Default")
      (node (ref "JP1") (pin "14") (pinfunction "14_14") (pintype "passive"))
      (node (ref "JP2") (pin "14") (pinfunction "14_14") (pintype "passive"))
      (node (ref "SHIFTOUTA") (pin "11") (pinfunction "SCK_11") (pintype "input"))
      (node (ref "SHIFTOUTB") (pin "11") (pinfunction "SCK_11") (pintype "input"))
      (node (ref "SHIFTOUTC") (pin "11") (pinfunction "SCK_11") (pintype "input"))
      (node (ref "SHIFTOUTD") (pin "11") (pinfunction "SCK_11") (pintype "input"))
      (node (ref "SHIFTOUTE") (pin "11") (pinfunction "SCK_11") (pintype "input"))
    )
    (net (code "137") (name "SR_DS") (class "Default")
      (node (ref "JP1") (pin "10") (pinfunction "10_10") (pintype "passive"))
      (node (ref "SHIFTOUTA") (pin "14") (pinfunction "SER_14") (pintype "input"))
    )
    (net (code "138") (name "SR_DS_2") (class "Default")
      (node (ref "JP2") (pin "10") (pinfunction "10_10") (pintype "passive"))
      (node (ref "SHIFTOUTE") (pin "9") (pinfunction "QH*_9") (pintype "tri_state"))
    )
    (net (code "139") (name "SR_RST") (class "Default")
      (node (ref "JP1") (pin "16") (pinfunction "16_16") (pintype "passive"))
      (node (ref "JP2") (pin "16") (pinfunction "16_16") (pintype "passive"))
      (node (ref "SHIFTOUTA") (pin "10") (pinfunction "SCL_10") (pintype "input"))
      (node (ref "SHIFTOUTB") (pin "10") (pinfunction "SCL_10") (pintype "input"))
      (node (ref "SHIFTOUTC") (pin "10") (pinfunction "SCL_10") (pintype "input"))
      (node (ref "SHIFTOUTD") (pin "10") (pinfunction "SCL_10") (pintype "input"))
      (node (ref "SHIFTOUTE") (pin "10") (pinfunction "SCL_10") (pintype "input"))
    )
    (net (code "140") (name "STCP") (class "Default")
      (node (ref "JP1") (pin "12") (pinfunction "12_12") (pintype "passive"))
      (node (ref "JP2") (pin "12") (pinfunction "12_12") (pintype "passive"))
      (node (ref "SHIFTOUTA") (pin "12") (pinfunction "RCK_12") (pintype "input"))
      (node (ref "SHIFTOUTB") (pin "12") (pinfunction "RCK_12") (pintype "input"))
      (node (ref "SHIFTOUTC") (pin "12") (pinfunction "RCK_12") (pintype "input"))
      (node (ref "SHIFTOUTD") (pin "12") (pinfunction "RCK_12") (pintype "input"))
      (node (ref "SHIFTOUTE") (pin "12") (pinfunction "RCK_12") (pintype "input"))
    )
    (net (code "141") (name "VCC") (class "Default")
      (node (ref "C1") (pin "1") (pinfunction "1_1") (pintype "passive"))
      (node (ref "C2") (pin "1") (pinfunction "1_1") (pintype "passive"))
      (node (ref "C3") (pin "1") (pinfunction "1_1") (pintype "passive"))
      (node (ref "C4") (pin "1") (pinfunction "1_1") (pintype "passive"))
      (node (ref "C5") (pin "1") (pinfunction "1_1") (pintype "passive"))
      (node (ref "JP1") (pin "1") (pinfunction "1_1") (pintype "passive"))
      (node (ref "JP1") (pin "3") (pinfunction "3_3") (pintype "passive"))
      (node (ref "JP1") (pin "5") (pinfunction "5_5") (pintype "passive"))
      (node (ref "JP1") (pin "7") (pinfunction "7_7") (pintype "passive"))
      (node (ref "JP2") (pin "1") (pinfunction "1_1") (pintype "passive"))
      (node (ref "JP2") (pin "3") (pinfunction "3_3") (pintype "passive"))
      (node (ref "JP2") (pin "5") (pinfunction "5_5") (pintype "passive"))
      (node (ref "JP2") (pin "7") (pinfunction "7_7") (pintype "passive"))
      (node (ref "RN1") (pin "1") (pinfunction "1_1") (pintype "passive"))
      (node (ref "RN2") (pin "1") (pinfunction "1_1") (pintype "passive"))
      (node (ref "RN3") (pin "1") (pinfunction "1_1") (pintype "passive"))
      (node (ref "RN4") (pin "1") (pinfunction "1_1") (pintype "passive"))
      (node (ref "RN5") (pin "1") (pinfunction "1_1") (pintype "passive"))
      (node (ref "SHIFT1") (pin "16") (pinfunction "VCC_16") (pintype "power_in"))
      (node (ref "SHIFT2") (pin "16") (pinfunction "VCC_16") (pintype "power_in"))
      (node (ref "SHIFT3") (pin "16") (pinfunction "VCC_16") (pintype "power_in"))
      (node (ref "SHIFT4") (pin "16") (pinfunction "VCC_16") (pintype "power_in"))
      (node (ref "SHIFT5") (pin "16") (pinfunction "VCC_16") (pintype "power_in"))
      (node (ref "SHIFTOUTA") (pin "16") (pinfunction "VCC_16") (pintype "power_in"))
      (node (ref "SHIFTOUTB") (pin "16") (pinfunction "VCC_16") (pintype "power_in"))
      (node (ref "SHIFTOUTC") (pin "16") (pinfunction "VCC_16") (pintype "power_in"))
      (node (ref "SHIFTOUTD") (pin "16") (pinfunction "VCC_16") (pintype "power_in"))
      (node (ref "SHIFTOUTE") (pin "16") (pinfunction "VCC_16") (pintype "power_in"))
    )
    (net (code "142") (name "unconnected-(SHIFT1A-~{QH}-Pad7)") (class "Default")
      (node (ref "SHIFT1") (pin "7") (pinfunction "~{QH}_7") (pintype "output"))
    )
    (net (code "143") (name "unconnected-(SHIFT2A-~{QH}-Pad7)") (class "Default")
      (node (ref "SHIFT2") (pin "7") (pinfunction "~{QH}_7") (pintype "output"))
    )
    (net (code "144") (name "unconnected-(SHIFT3A-~{QH}-Pad7)") (class "Default")
      (node (ref "SHIFT3") (pin "7") (pinfunction "~{QH}_7") (pintype "output"))
    )
    (net (code "145") (name "unconnected-(SHIFT4A-~{QH}-Pad7)") (class "Default")
      (node (ref "SHIFT4") (pin "7") (pinfunction "~{QH}_7") (pintype "output"))
    )
    (net (code "146") (name "unconnected-(SHIFT5A-~{QH}-Pad7)") (class "Default")
      (node (ref "SHIFT5") (pin "7") (pinfunction "~{QH}_7") (pintype "output"))
    )
  )
)
